# OPENMV4_wd.net
KiCad netlist of a schematic drawn in Altium Designer
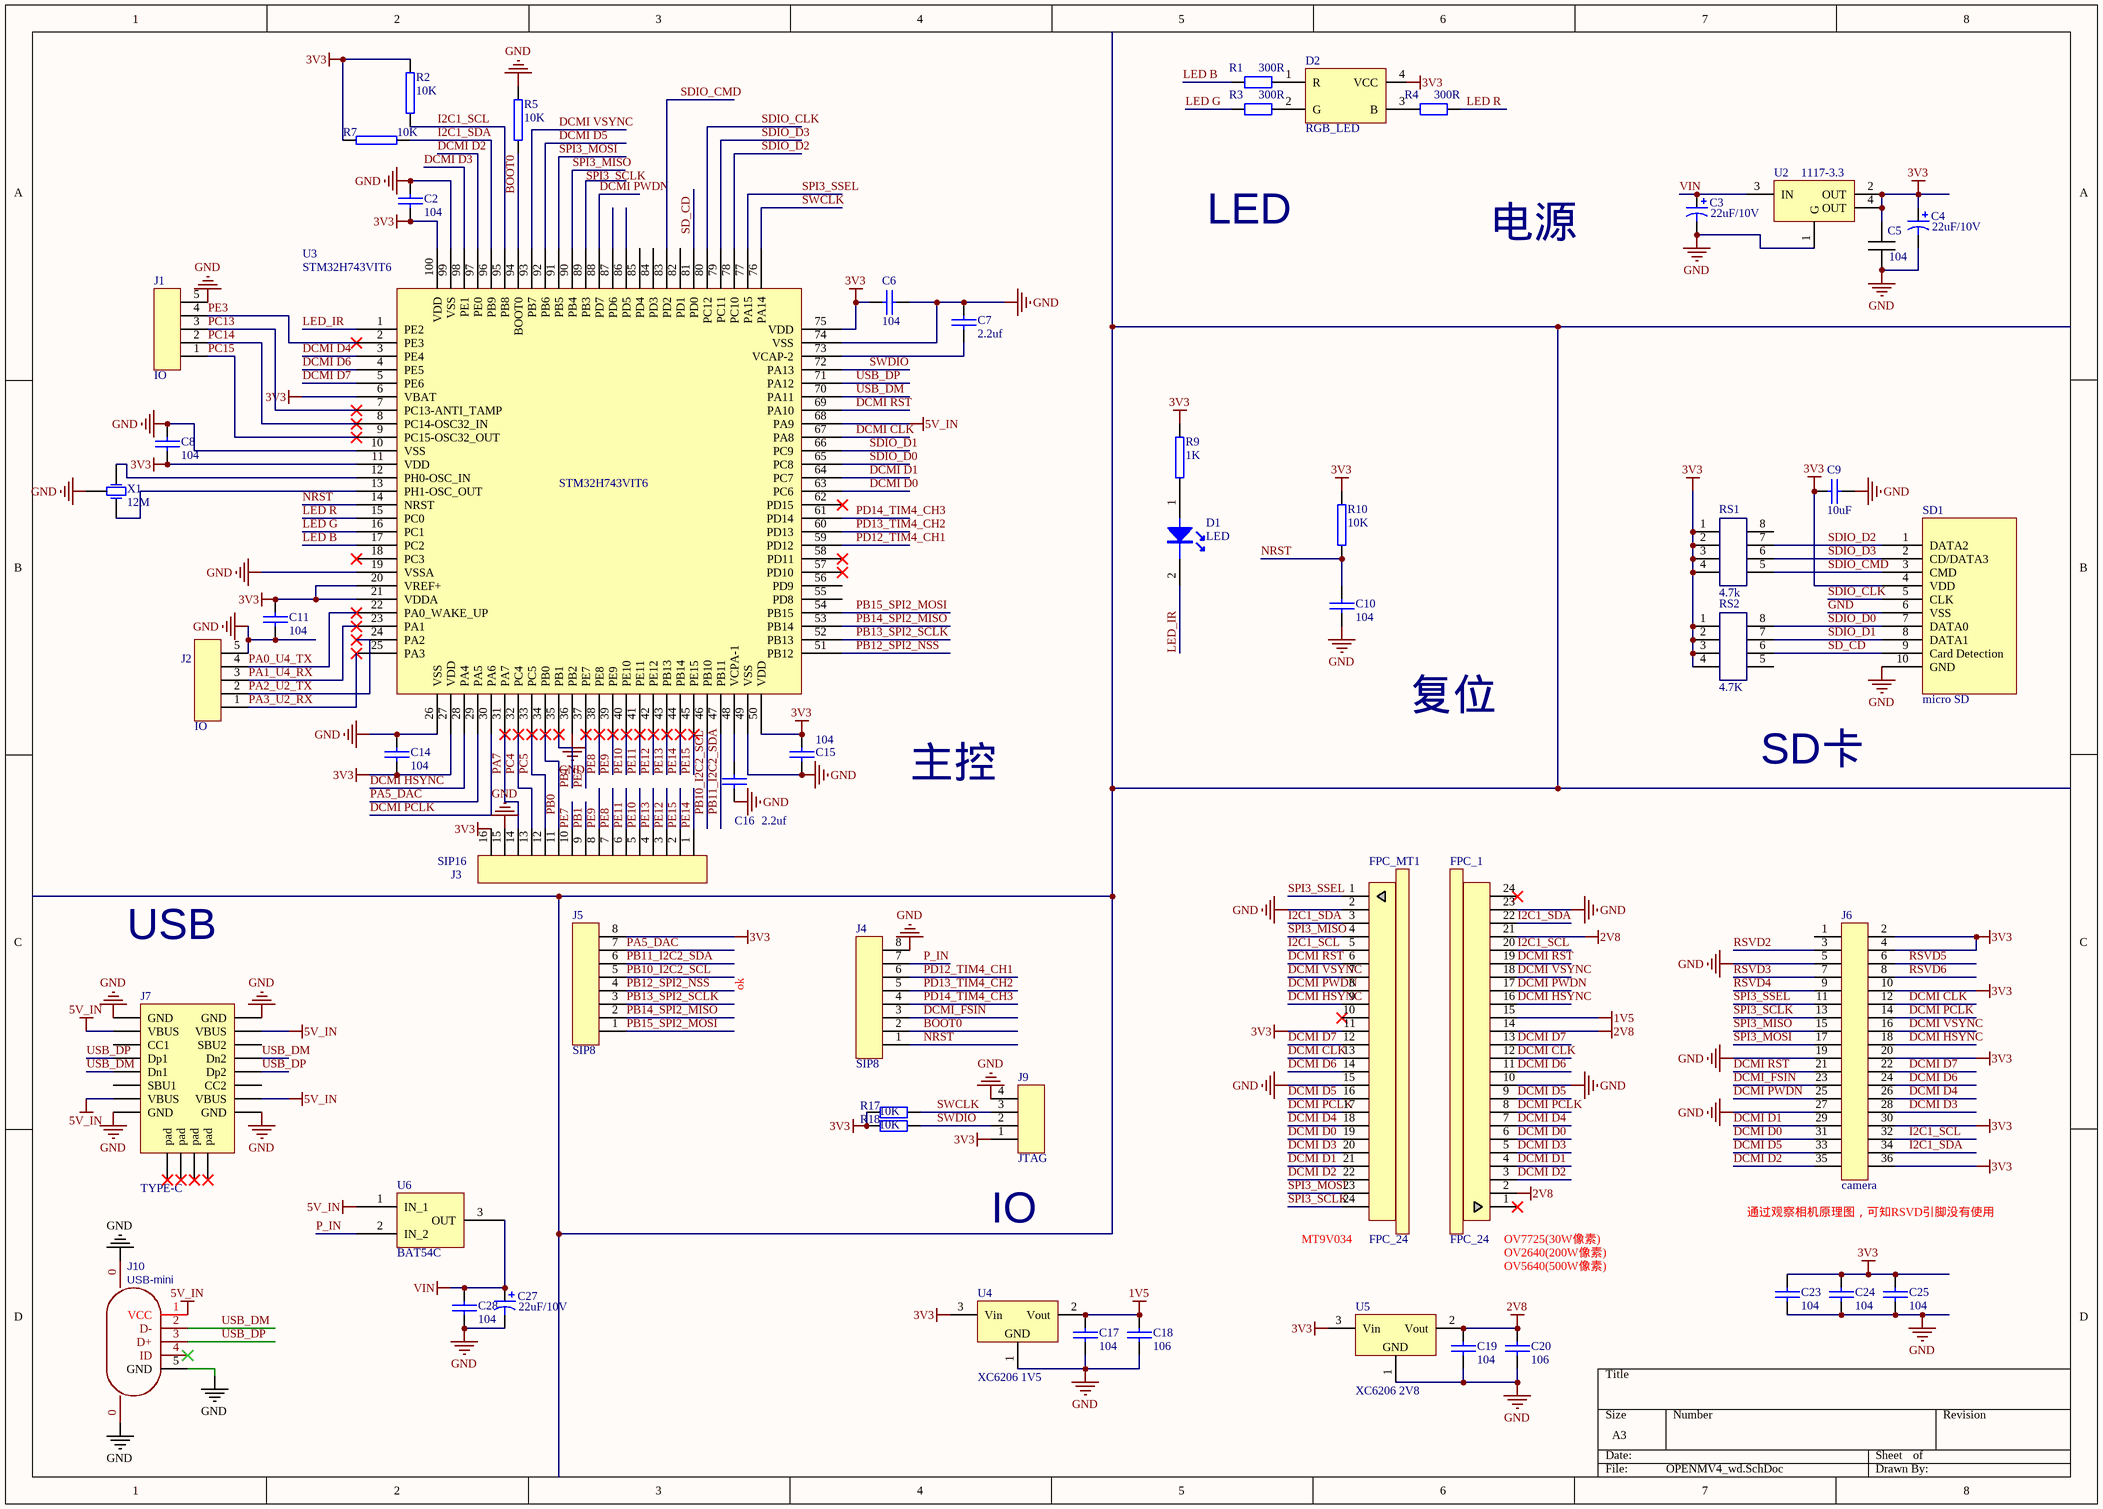
[diagram p0: OPENMV4_wd.SchDoc]

(export (version "E")
  (design (tool "Eeschema 10.0.6"))
  (components
    (comp (ref "C2") (value "104") (footprint "0805C") (libsource (lib "自创 (1)") (part "CAP")))
    (comp (ref "C3")
      (value "22uF/10V")
      (footprint "1210")
      (description "Polarized Capacitor (Radial)")
      (fields (field (name "Comment") "47uF") (field (name "PUBLISHER") "Altium Limited"))
      (libsource (lib "Miscellaneous Devices") (part "Cap Pol1"))
    )
    (comp (ref "C4")
      (value "22uF/10V")
      (footprint "1210")
      (description "Polarized Capacitor (Radial)")
      (fields (field (name "Comment") "47uF") (field (name "PUBLISHER") "Altium Limited"))
      (libsource (lib "Miscellaneous Devices") (part "Cap Pol1"))
    )
    (comp (ref "C5") (value "104") (footprint "0805C") (libsource (lib "NT-SchLibrary") (part "CAP104")))
    (comp (ref "C6") (value "104") (footprint "0805C") (libsource (lib "自创 (1)") (part "CAP")))
    (comp (ref "C7") (value "2.2uf") (footprint "0805C") (libsource (lib "自创 (1)") (part "CAP")))
    (comp (ref "C8") (value "104") (footprint "0805C") (libsource (lib "自创 (1)") (part "CAP")))
    (comp (ref "C9") (value "10uF") (footprint "LC-0805_C") (libsource (lib "自创 (1)") (part "CAP")))
    (comp (ref "C10") (value "104") (footprint "0805C") (libsource (lib "自创 (1)") (part "CAP")))
    (comp (ref "C11") (value "104") (footprint "0805C") (libsource (lib "自创 (1)") (part "CAP")))
    (comp (ref "C14") (value "104") (footprint "0805C") (libsource (lib "自创 (1)") (part "CAP")))
    (comp (ref "C15") (value "104") (footprint "0805C") (libsource (lib "自创 (1)") (part "CAP")))
    (comp (ref "C16") (value "2.2uf") (footprint "0805C") (libsource (lib "自创 (1)") (part "CAP")))
    (comp (ref "C17") (value "104") (footprint "0805C") (libsource (lib "XKZ") (part "CAP")))
    (comp (ref "C18") (value "106") (footprint "0805C") (libsource (lib "XKZ") (part "CAP")))
    (comp (ref "C19") (value "104") (footprint "0805C") (libsource (lib "XKZ") (part "CAP")))
    (comp (ref "C20") (value "106") (footprint "0805C") (libsource (lib "XKZ") (part "CAP")))
    (comp (ref "C23") (value "104") (footprint "0805C") (libsource (lib "自创 (1)") (part "CAP")))
    (comp (ref "C24") (value "104") (footprint "0805C") (libsource (lib "自创 (1)") (part "CAP")))
    (comp (ref "C25") (value "104") (footprint "0805C") (libsource (lib "自创 (1)") (part "CAP")))
    (comp (ref "C27")
      (value "22uF/10V")
      (footprint "1210")
      (description "Polarized Capacitor (Radial)")
      (fields (field (name "Comment") "47uF") (field (name "PUBLISHER") "Altium Limited"))
      (libsource (lib "Miscellaneous Devices") (part "Cap Pol1"))
    )
    (comp (ref "C28") (value "104") (footprint "0805C") (libsource (lib "自创 (1)") (part "CAP")))
    (comp (ref "D1") (value "LED") (footprint "0805D") (libsource (lib "WindSCH") (part "LED")))
    (comp (ref "D2")
      (value "RGB_LED")
      (footprint "LED_3528_RGB")
      (description "三色高亮LED")
      (libsource (lib "NT-SchLibrary") (part "RGB_LED"))
    )
    (comp (ref "FPC_1") (value "FPC_24") (footprint "FPC_24") (libsource (lib "") (part "FPC_24_1")))
    (comp (ref "FPC_MT1") (value "FPC_24") (footprint "FPC_24") (libsource (lib "XKZ") (part "FPC_24")))
    (comp (ref "J1") (value "IO") (footprint "SIP5") (libsource (lib "WindSCH") (part "SIP5")))
    (comp (ref "J2") (value "IO") (footprint "SIP5") (libsource (lib "WindSCH") (part "SIP5")))
    (comp (ref "J3") (value "SIP16") (footprint "IDC16") (libsource (lib "WindSCH") (part "SIP16")))
    (comp (ref "J4") (value "SIP8") (footprint "sip8") (libsource (lib "WindSCH") (part "SIP8")))
    (comp (ref "J5") (value "SIP8") (footprint "sip8") (libsource (lib "WindSCH") (part "SIP8")))
    (comp (ref "J6") (value "camera") (footprint "DF12-36-DS") (libsource (lib "WindSCH") (part "IDC36")))
    (comp (ref "J7") (value "TYPE-C") (footprint "USB Type-C-16Pin_A") (libsource (lib "XKZ") (part "USB_C")))
    (comp (ref "J9") (value "JTAG") (footprint "SIP4-1") (libsource (lib "WindSCH") (part "SIP4")))
    (comp (ref "J10")
      (value "USB-mini")
      (footprint "USB-MINI")
      (fields
        (field (name "BOM_MANUFACTURER PART") "USB-CON-MICRO-B-5S")
        (field (name "BOM_SUPPLIER PART") "C40954")
      )
      (libsource (lib "crazepony2_1") (part "USB-CON-MICRO-B-5S"))
    )
    (comp (ref "R1")
      (value "300R")
      (footprint "0805R")
      (description "Resistor")
      (fields (field (name "Comment") "1K") (field (name "PUBLISHER") "Altium Limited"))
      (libsource (lib "Miscellaneous Devices") (part "Res2"))
    )
    (comp (ref "R2") (value "10K") (footprint "0805R") (libsource (lib "自创 (1)") (part "RES")))
    (comp (ref "R3")
      (value "300R")
      (footprint "0805R")
      (description "Resistor")
      (fields (field (name "Comment") "1K") (field (name "PUBLISHER") "Altium Limited"))
      (libsource (lib "Miscellaneous Devices") (part "Res2"))
    )
    (comp (ref "R4")
      (value "300R")
      (footprint "0805R")
      (description "Resistor")
      (fields (field (name "Comment") "1K") (field (name "PUBLISHER") "Altium Limited"))
      (libsource (lib "Miscellaneous Devices") (part "Res2"))
    )
    (comp (ref "R5") (value "10K") (footprint "0805R") (libsource (lib "自创 (1)") (part "RES")))
    (comp (ref "R7") (value "10K") (footprint "0805R") (libsource (lib "自创 (1)") (part "RES")))
    (comp (ref "R9") (value "1K") (footprint "0805R") (libsource (lib "自创 (1)") (part "RES")))
    (comp (ref "R10") (value "10K") (footprint "0805R") (libsource (lib "自创 (1)") (part "RES")))
    (comp (ref "R17")
      (value "10K")
      (footprint "0805R")
      (description "Resistor")
      (fields (field (name "PUBLISHER") "Altium Limited"))
      (libsource (lib "") (part "Res2_1"))
    )
    (comp (ref "R18")
      (value "10K")
      (footprint "0805R")
      (description "Resistor")
      (fields (field (name "PUBLISHER") "Altium Limited"))
      (libsource (lib "") (part "Res2_1"))
    )
    (comp (ref "RS1") (value "4.7k") (footprint "0603*4") (libsource (lib "WindSCH") (part "RS")))
    (comp (ref "RS2") (value "4.7K") (footprint "0603*4") (libsource (lib "WindSCH") (part "RS")))
    (comp (ref "SD1") (value "micro SD") (footprint "TF卡座") (libsource (lib "XKZ") (part "micro SD")))
    (comp (ref "U2") (value "1117-3.3") (footprint "SOT223") (libsource (lib "WindSCH") (part "1117")))
    (comp (ref "U3")
      (value "STM32H743VIT6")
      (footprint "LQFP100 14x14_N")
      (libsource (lib "XKZ") (part "STM32H743VIT6"))
    )
    (comp (ref "U4")
      (value "XC6206 1V5")
      (footprint "SOT23-3N")
      (description "低压差线性稳压芯片")
      (fields (field (name "版权归属") "源创客"))
      (libsource (lib "XKZ") (part "XC6206P332MR"))
    )
    (comp (ref "U5")
      (value "XC6206 2V8")
      (footprint "SOT23-3N")
      (description "低压差线性稳压芯片")
      (fields (field (name "版权归属") "源创客"))
      (libsource (lib "XKZ") (part "XC6206P332MR"))
    )
    (comp (ref "U6") (value "BAT54C") (footprint "SOT23-3N") (libsource (lib "XKZ") (part "BAT54C")))
    (comp (ref "X1") (value "12M") (footprint "XTAL-3215-3P") (libsource (lib "XKZ") (part "XTAL_3P")))
  )
  (nets
    (net (code "1") (name "/BOOT0") (class "Default")
      (node (ref "J4") (pin "2") (pintype "passive"))
      (node (ref "R5") (pin "1") (pinfunction "1_1") (pintype "passive"))
      (node (ref "U3") (pin "94") (pinfunction "BOOT0_94") (pintype "passive"))
    )
    (net (code "2") (name "/DCMI CLK") (class "Default")
      (node (ref "FPC_1") (pin "12") (pinfunction "12_12") (pintype "passive"))
      (node (ref "FPC_MT1") (pin "13") (pinfunction "13_13") (pintype "passive"))
      (node (ref "J6") (pin "12") (pintype "passive"))
      (node (ref "U3") (pin "67") (pinfunction "PA8_67") (pintype "passive"))
    )
    (net (code "3") (name "/DCMI D0") (class "Default")
      (node (ref "FPC_1") (pin "6") (pinfunction "6_6") (pintype "passive"))
      (node (ref "FPC_MT1") (pin "19") (pinfunction "19_19") (pintype "passive"))
      (node (ref "J6") (pin "31") (pintype "passive"))
      (node (ref "U3") (pin "63") (pinfunction "PC6_63") (pintype "passive"))
    )
    (net (code "4") (name "/DCMI D1") (class "Default")
      (node (ref "FPC_1") (pin "4") (pinfunction "4_4") (pintype "passive"))
      (node (ref "FPC_MT1") (pin "21") (pinfunction "21_21") (pintype "passive"))
      (node (ref "J6") (pin "29") (pintype "passive"))
      (node (ref "U3") (pin "64") (pinfunction "PC7_64") (pintype "passive"))
    )
    (net (code "5") (name "/DCMI D2") (class "Default")
      (node (ref "FPC_1") (pin "3") (pinfunction "3_3") (pintype "passive"))
      (node (ref "FPC_MT1") (pin "22") (pinfunction "22_22") (pintype "passive"))
      (node (ref "J6") (pin "35") (pintype "passive"))
      (node (ref "U3") (pin "97") (pinfunction "PE0_97") (pintype "passive"))
    )
    (net (code "6") (name "/DCMI D3") (class "Default")
      (node (ref "FPC_1") (pin "5") (pinfunction "5_5") (pintype "passive"))
      (node (ref "FPC_MT1") (pin "20") (pinfunction "20_20") (pintype "passive"))
      (node (ref "J6") (pin "28") (pintype "passive"))
      (node (ref "U3") (pin "98") (pinfunction "PE1_98") (pintype "passive"))
    )
    (net (code "7") (name "/DCMI D4") (class "Default")
      (node (ref "FPC_1") (pin "7") (pinfunction "7_7") (pintype "passive"))
      (node (ref "FPC_MT1") (pin "18") (pinfunction "18_18") (pintype "passive"))
      (node (ref "J6") (pin "26") (pintype "passive"))
      (node (ref "U3") (pin "3") (pinfunction "PE4_3") (pintype "passive"))
    )
    (net (code "8") (name "/DCMI D5") (class "Default")
      (node (ref "FPC_1") (pin "9") (pinfunction "9_9") (pintype "passive"))
      (node (ref "FPC_MT1") (pin "16") (pinfunction "16_16") (pintype "passive"))
      (node (ref "J6") (pin "33") (pintype "passive"))
      (node (ref "U3") (pin "92") (pinfunction "PB6_92") (pintype "passive"))
    )
    (net (code "9") (name "/DCMI D6") (class "Default")
      (node (ref "FPC_1") (pin "11") (pinfunction "11_11") (pintype "passive"))
      (node (ref "FPC_MT1") (pin "14") (pinfunction "14_14") (pintype "passive"))
      (node (ref "J6") (pin "24") (pintype "passive"))
      (node (ref "U3") (pin "4") (pinfunction "PE5_4") (pintype "passive"))
    )
    (net (code "10") (name "/DCMI D7") (class "Default")
      (node (ref "FPC_1") (pin "13") (pinfunction "13_13") (pintype "passive"))
      (node (ref "FPC_MT1") (pin "12") (pinfunction "12_12") (pintype "passive"))
      (node (ref "J6") (pin "22") (pintype "passive"))
      (node (ref "U3") (pin "5") (pinfunction "PE6_5") (pintype "passive"))
    )
    (net (code "11") (name "/DCMI HSYNC") (class "Default")
      (node (ref "FPC_1") (pin "16") (pinfunction "16_16") (pintype "passive"))
      (node (ref "FPC_MT1") (pin "9") (pinfunction "9_9") (pintype "passive"))
      (node (ref "J6") (pin "18") (pintype "passive"))
      (node (ref "U3") (pin "28") (pinfunction "PA4_28") (pintype "passive"))
    )
    (net (code "12") (name "/DCMI PCLK") (class "Default")
      (node (ref "FPC_1") (pin "8") (pinfunction "8_8") (pintype "passive"))
      (node (ref "FPC_MT1") (pin "17") (pinfunction "17_17") (pintype "passive"))
      (node (ref "J6") (pin "14") (pintype "passive"))
      (node (ref "U3") (pin "30") (pinfunction "PA6_30") (pintype "passive"))
    )
    (net (code "13") (name "/DCMI PWDN") (class "Default")
      (node (ref "FPC_1") (pin "17") (pinfunction "17_17") (pintype "passive"))
      (node (ref "FPC_MT1") (pin "8") (pinfunction "8_8") (pintype "passive"))
      (node (ref "J6") (pin "25") (pintype "passive"))
      (node (ref "U3") (pin "88") (pinfunction "PD7_88") (pintype "passive"))
    )
    (net (code "14") (name "/DCMI RST") (class "Default")
      (node (ref "FPC_1") (pin "19") (pinfunction "19_19") (pintype "passive"))
      (node (ref "FPC_MT1") (pin "6") (pinfunction "6_6") (pintype "passive"))
      (node (ref "J6") (pin "21") (pintype "passive"))
      (node (ref "U3") (pin "69") (pinfunction "PA10_69") (pintype "passive"))
    )
    (net (code "15") (name "/DCMI VSYNC") (class "Default")
      (node (ref "FPC_1") (pin "18") (pinfunction "18_18") (pintype "passive"))
      (node (ref "FPC_MT1") (pin "7") (pinfunction "7_7") (pintype "passive"))
      (node (ref "J6") (pin "16") (pintype "passive"))
      (node (ref "U3") (pin "93") (pinfunction "PB7_93") (pintype "passive"))
    )
    (net (code "16") (name "/DCMI_FSIN") (class "Default")
      (node (ref "J4") (pin "3") (pintype "passive"))
      (node (ref "J6") (pin "23") (pintype "passive"))
    )
    (net (code "17") (name "/I2C1_SCL") (class "Default")
      (node (ref "FPC_1") (pin "20") (pinfunction "20_20") (pintype "passive"))
      (node (ref "FPC_MT1") (pin "5") (pinfunction "5_5") (pintype "passive"))
      (node (ref "J6") (pin "32") (pintype "passive"))
      (node (ref "R2") (pin "1") (pinfunction "1_1") (pintype "passive"))
      (node (ref "U3") (pin "95") (pinfunction "PB8_95") (pintype "passive"))
    )
    (net (code "18") (name "/I2C1_SDA") (class "Default")
      (node (ref "FPC_1") (pin "22") (pinfunction "22_22") (pintype "passive"))
      (node (ref "FPC_MT1") (pin "3") (pinfunction "3_3") (pintype "passive"))
      (node (ref "J6") (pin "34") (pintype "passive"))
      (node (ref "R7") (pin "2") (pinfunction "2_2") (pintype "passive"))
      (node (ref "U3") (pin "96") (pinfunction "PB9_96") (pintype "passive"))
    )
    (net (code "19") (name "/LED B") (class "Default")
      (node (ref "R1") (pin "1") (pinfunction "1_1") (pintype "passive"))
      (node (ref "U3") (pin "17") (pinfunction "PC2_17") (pintype "passive"))
    )
    (net (code "20") (name "/LED G") (class "Default")
      (node (ref "R3") (pin "1") (pinfunction "1_1") (pintype "passive"))
      (node (ref "U3") (pin "16") (pinfunction "PC1_16") (pintype "passive"))
    )
    (net (code "21") (name "/LED R") (class "Default")
      (node (ref "R4") (pin "2") (pinfunction "2_2") (pintype "passive"))
      (node (ref "U3") (pin "15") (pinfunction "PC0_15") (pintype "passive"))
    )
    (net (code "22") (name "/LED_IR") (class "Default")
      (node (ref "D1") (pin "2") (pinfunction "2_2") (pintype "passive"))
      (node (ref "U3") (pin "1") (pinfunction "PE2_1") (pintype "passive"))
    )
    (net (code "23") (name "/NRST") (class "Default")
      (node (ref "C10") (pin "2") (pinfunction "2_2") (pintype "passive"))
      (node (ref "J4") (pin "1") (pintype "passive"))
      (node (ref "R10") (pin "2") (pinfunction "2_2") (pintype "passive"))
      (node (ref "U3") (pin "14") (pinfunction "NRST_14") (pintype "passive"))
    )
    (net (code "24") (name "/PA0_U4_TX") (class "Default")
      (node (ref "J2") (pin "4") (pintype "passive"))
      (node (ref "U3") (pin "22") (pinfunction "PA0_WAKE_UP_22") (pintype "passive"))
    )
    (net (code "25") (name "/PA1_U4_RX") (class "Default")
      (node (ref "J2") (pin "3") (pintype "passive"))
      (node (ref "U3") (pin "23") (pinfunction "PA1_23") (pintype "passive"))
    )
    (net (code "26") (name "/PA2_U2_TX") (class "Default")
      (node (ref "J2") (pin "2") (pintype "passive"))
      (node (ref "U3") (pin "24") (pinfunction "PA2_24") (pintype "passive"))
    )
    (net (code "27") (name "/PA3_U2_RX") (class "Default")
      (node (ref "J2") (pin "1") (pintype "passive"))
      (node (ref "U3") (pin "25") (pinfunction "PA3_25") (pintype "passive"))
    )
    (net (code "28") (name "/PA5_DAC") (class "Default")
      (node (ref "J5") (pin "7") (pintype "passive"))
      (node (ref "U3") (pin "29") (pinfunction "PA5_29") (pintype "passive"))
    )
    (net (code "29") (name "/PA7") (class "Default")
      (node (ref "J3") (pin "14") (pintype "passive"))
      (node (ref "U3") (pin "31") (pinfunction "PA7_31") (pintype "passive"))
    )
    (net (code "30") (name "/PB0") (class "Default")
      (node (ref "J3") (pin "11") (pintype "passive"))
      (node (ref "U3") (pin "34") (pinfunction "PB0_34") (pintype "passive"))
    )
    (net (code "31") (name "/PB1") (class "Default")
      (node (ref "J3") (pin "9") (pintype "passive"))
      (node (ref "U3") (pin "35") (pinfunction "PB1_35") (pintype "passive"))
    )
    (net (code "32") (name "/PB10_I2C2_SCL") (class "Default")
      (node (ref "J5") (pin "5") (pintype "passive"))
      (node (ref "U3") (pin "46") (pinfunction "PB10_46") (pintype "passive"))
    )
    (net (code "33") (name "/PB11_I2C2_SDA") (class "Default")
      (node (ref "J5") (pin "6") (pintype "passive"))
      (node (ref "U3") (pin "47") (pinfunction "PB11_47") (pintype "passive"))
    )
    (net (code "34") (name "/PB12_SPI2_NSS") (class "Default")
      (node (ref "J5") (pin "4") (pintype "passive"))
      (node (ref "U3") (pin "51") (pinfunction "PB12_51") (pintype "passive"))
    )
    (net (code "35") (name "/PB13_SPI2_SCLK") (class "Default")
      (node (ref "J5") (pin "3") (pintype "passive"))
      (node (ref "U3") (pin "52") (pinfunction "PB13_52") (pintype "passive"))
    )
    (net (code "36") (name "/PB14_SPI2_MISO") (class "Default")
      (node (ref "J5") (pin "2") (pintype "passive"))
      (node (ref "U3") (pin "53") (pinfunction "PB14_53") (pintype "passive"))
    )
    (net (code "37") (name "/PB15_SPI2_MOSI") (class "Default")
      (node (ref "J5") (pin "1") (pintype "passive"))
      (node (ref "U3") (pin "54") (pinfunction "PB15_54") (pintype "passive"))
    )
    (net (code "38") (name "/PC4") (class "Default")
      (node (ref "J3") (pin "13") (pintype "passive"))
      (node (ref "U3") (pin "32") (pinfunction "PC4_32") (pintype "passive"))
    )
    (net (code "39") (name "/PC5") (class "Default")
      (node (ref "J3") (pin "12") (pintype "passive"))
      (node (ref "U3") (pin "33") (pinfunction "PC5_33") (pintype "passive"))
    )
    (net (code "40") (name "/PC13") (class "Default")
      (node (ref "J1") (pin "3") (pintype "passive"))
      (node (ref "U3") (pin "7") (pinfunction "PC13-ANTI_TAMP_7") (pintype "passive"))
    )
    (net (code "41") (name "/PC14") (class "Default")
      (node (ref "J1") (pin "2") (pintype "passive"))
      (node (ref "U3") (pin "8") (pinfunction "PC14-OSC32_IN_8") (pintype "passive"))
    )
    (net (code "42") (name "/PC15") (class "Default")
      (node (ref "J1") (pin "1") (pintype "passive"))
      (node (ref "U3") (pin "9") (pinfunction "PC15-OSC32_OUT_9") (pintype "passive"))
    )
    (net (code "43") (name "/PD12_TIM4_CH1") (class "Default")
      (node (ref "J4") (pin "6") (pintype "passive"))
      (node (ref "U3") (pin "59") (pinfunction "PD12_59") (pintype "passive"))
    )
    (net (code "44") (name "/PD13_TIM4_CH2") (class "Default")
      (node (ref "J4") (pin "5") (pintype "passive"))
      (node (ref "U3") (pin "60") (pinfunction "PD13_60") (pintype "passive"))
    )
    (net (code "45") (name "/PD14_TIM4_CH3") (class "Default")
      (node (ref "J4") (pin "4") (pintype "passive"))
      (node (ref "U3") (pin "61") (pinfunction "PD14_61") (pintype "passive"))
    )
    (net (code "46") (name "/PE3") (class "Default")
      (node (ref "J1") (pin "4") (pintype "passive"))
      (node (ref "U3") (pin "2") (pinfunction "PE3_2") (pintype "passive"))
    )
    (net (code "47") (name "/PE7") (class "Default")
      (node (ref "J3") (pin "10") (pintype "passive"))
      (node (ref "U3") (pin "37") (pinfunction "PE7_37") (pintype "passive"))
    )
    (net (code "48") (name "/PE8") (class "Default")
      (node (ref "J3") (pin "7") (pintype "passive"))
      (node (ref "U3") (pin "38") (pinfunction "PE8_38") (pintype "passive"))
    )
    (net (code "49") (name "/PE9") (class "Default")
      (node (ref "J3") (pin "8") (pintype "passive"))
      (node (ref "U3") (pin "39") (pinfunction "PE9_39") (pintype "passive"))
    )
    (net (code "50") (name "/PE10") (class "Default")
      (node (ref "J3") (pin "5") (pintype "passive"))
      (node (ref "U3") (pin "40") (pinfunction "PE10_40") (pintype "passive"))
    )
    (net (code "51") (name "/PE11") (class "Default")
      (node (ref "J3") (pin "6") (pintype "passive"))
      (node (ref "U3") (pin "41") (pinfunction "PE11_41") (pintype "passive"))
    )
    (net (code "52") (name "/PE12") (class "Default")
      (node (ref "J3") (pin "3") (pintype "passive"))
      (node (ref "U3") (pin "42") (pinfunction "PE12_42") (pintype "passive"))
    )
    (net (code "53") (name "/PE13") (class "Default")
      (node (ref "J3") (pin "4") (pintype "passive"))
      (node (ref "U3") (pin "43") (pinfunction "PB13_43") (pintype "passive"))
    )
    (net (code "54") (name "/PE14") (class "Default")
      (node (ref "J3") (pin "1") (pintype "passive"))
      (node (ref "U3") (pin "44") (pinfunction "PB14_44") (pintype "passive"))
    )
    (net (code "55") (name "/PE15") (class "Default")
      (node (ref "J3") (pin "2") (pintype "passive"))
      (node (ref "U3") (pin "45") (pinfunction "PE15_45") (pintype "passive"))
    )
    (net (code "56") (name "/P_IN") (class "Default")
      (node (ref "J4") (pin "7") (pintype "passive"))
      (node (ref "U6") (pin "2") (pinfunction "IN_2_2") (pintype "passive"))
    )
    (net (code "57") (name "/RSVD2") (class "Default") (node (ref "J6") (pin "3") (pintype "passive")))
    (net (code "58") (name "/RSVD3") (class "Default") (node (ref "J6") (pin "7") (pintype "passive")))
    (net (code "59") (name "/RSVD4") (class "Default") (node (ref "J6") (pin "9") (pintype "passive")))
    (net (code "60") (name "/RSVD5") (class "Default") (node (ref "J6") (pin "6") (pintype "passive")))
    (net (code "61") (name "/RSVD6") (class "Default") (node (ref "J6") (pin "8") (pintype "passive")))
    (net (code "62") (name "/SDIO_CLK") (class "Default")
      (node (ref "SD1") (pin "5") (pinfunction "CLK_5") (pintype "passive"))
      (node (ref "U3") (pin "80") (pinfunction "PC12_80") (pintype "passive"))
    )
    (net (code "63") (name "/SDIO_CMD") (class "Default")
      (node (ref "RS1") (pin "5") (pinfunction "21_5") (pintype "passive"))
      (node (ref "SD1") (pin "3") (pinfunction "CMD_3") (pintype "passive"))
      (node (ref "U3") (pin "83") (pinfunction "PD2_83") (pintype "passive"))
    )
    (net (code "64") (name "/SDIO_D0") (class "Default")
      (node (ref "RS2") (pin "8") (pinfunction "24_8") (pintype "passive"))
      (node (ref "SD1") (pin "7") (pinfunction "DATA0_7") (pintype "passive"))
      (node (ref "U3") (pin "65") (pinfunction "PC8_65") (pintype "passive"))
    )
    (net (code "65") (name "/SDIO_D1") (class "Default")
      (node (ref "RS2") (pin "7") (pinfunction "23_7") (pintype "passive"))
      (node (ref "SD1") (pin "8") (pinfunction "DATA1_8") (pintype "passive"))
      (node (ref "U3") (pin "66") (pinfunction "PC9_66") (pintype "passive"))
    )
    (net (code "66") (name "/SDIO_D2") (class "Default")
      (node (ref "RS1") (pin "7") (pinfunction "23_7") (pintype "passive"))
      (node (ref "SD1") (pin "1") (pinfunction "DATA2_1") (pintype "passive"))
      (node (ref "U3") (pin "78") (pinfunction "PC10_78") (pintype "passive"))
    )
    (net (code "67") (name "/SDIO_D3") (class "Default")
      (node (ref "RS1") (pin "6") (pinfunction "22_6") (pintype "passive"))
      (node (ref "SD1") (pin "2") (pinfunction "CD/DATA3_2") (pintype "passive"))
      (node (ref "U3") (pin "79") (pinfunction "PC11_79") (pintype "passive"))
    )
    (net (code "68") (name "/SD_CD") (class "Default")
      (node (ref "RS2") (pin "6") (pinfunction "22_6") (pintype "passive"))
      (node (ref "SD1") (pin "9") (pinfunction "Card_Detection_9") (pintype "passive"))
      (node (ref "U3") (pin "81") (pinfunction "PD0_81") (pintype "passive"))
    )
    (net (code "69") (name "/SPI3_MISO") (class "Default")
      (node (ref "FPC_MT1") (pin "4") (pinfunction "4_4") (pintype "passive"))
      (node (ref "J6") (pin "15") (pintype "passive"))
      (node (ref "U3") (pin "90") (pinfunction "PB4_90") (pintype "passive"))
    )
    (net (code "70") (name "/SPI3_MOSI") (class "Default")
      (node (ref "FPC_MT1") (pin "23") (pinfunction "23_23") (pintype "passive"))
      (node (ref "J6") (pin "17") (pintype "passive"))
      (node (ref "U3") (pin "91") (pinfunction "PB5_91") (pintype "passive"))
    )
    (net (code "71") (name "/SPI3_SCLK") (class "Default")
      (node (ref "FPC_MT1") (pin "24") (pinfunction "24_24") (pintype "passive"))
      (node (ref "J6") (pin "13") (pintype "passive"))
      (node (ref "U3") (pin "89") (pinfunction "PB3_89") (pintype "passive"))
    )
    (net (code "72") (name "/SPI3_SSEL") (class "Default")
      (node (ref "FPC_MT1") (pin "1") (pinfunction "1_1") (pintype "passive"))
      (node (ref "J6") (pin "11") (pintype "passive"))
      (node (ref "U3") (pin "77") (pinfunction "PA15_77") (pintype "passive"))
    )
    (net (code "73") (name "/SWCLK") (class "Default")
      (node (ref "J9") (pin "3") (pintype "passive"))
      (node (ref "R17") (pin "1") (pinfunction "1_1") (pintype "passive"))
      (node (ref "U3") (pin "76") (pinfunction "PA14_76") (pintype "passive"))
    )
    (net (code "74") (name "/SWDIO") (class "Default")
      (node (ref "J9") (pin "2") (pintype "passive"))
      (node (ref "R18") (pin "1") (pinfunction "1_1") (pintype "passive"))
      (node (ref "U3") (pin "72") (pinfunction "PA13_72") (pintype "passive"))
    )
    (net (code "75") (name "/USB_DM") (class "Default")
      (node (ref "J10") (pin "2") (pinfunction "D-_2") (pintype "passive"))
      (node (ref "J7") (pin "A7") (pinfunction "Dn1_A7") (pintype "passive"))
      (node (ref "J7") (pin "B7") (pinfunction "Dn2_B7") (pintype "passive"))
      (node (ref "U3") (pin "70") (pinfunction "PA11_70") (pintype "passive"))
    )
    (net (code "76") (name "/USB_DP") (class "Default")
      (node (ref "J10") (pin "3") (pinfunction "D+_3") (pintype "passive"))
      (node (ref "J7") (pin "A6") (pinfunction "Dp1_A6") (pintype "passive"))
      (node (ref "J7") (pin "B6") (pinfunction "Dp2_B6") (pintype "passive"))
      (node (ref "U3") (pin "71") (pinfunction "PA12_71") (pintype "passive"))
    )
    (net (code "77") (name "1V5") (class "Default")
      (node (ref "C17") (pin "1") (pinfunction "1_1") (pintype "passive"))
      (node (ref "C18") (pin "1") (pinfunction "1_1") (pintype "passive"))
      (node (ref "FPC_1") (pin "15") (pinfunction "15_15") (pintype "passive"))
      (node (ref "U4") (pin "2") (pinfunction "Vout_2") (pintype "passive"))
    )
    (net (code "78") (name "2V8") (class "Default")
      (node (ref "C19") (pin "1") (pinfunction "1_1") (pintype "passive"))
      (node (ref "C20") (pin "1") (pinfunction "1_1") (pintype "passive"))
      (node (ref "FPC_1") (pin "14") (pinfunction "14_14") (pintype "passive"))
      (node (ref "FPC_1") (pin "2") (pinfunction "2_2") (pintype "passive"))
      (node (ref "FPC_1") (pin "21") (pinfunction "21_21") (pintype "passive"))
      (node (ref "U5") (pin "2") (pinfunction "Vout_2") (pintype "passive"))
    )
    (net (code "79") (name "3V3") (class "Default")
      (node (ref "C11") (pin "1") (pinfunction "1_1") (pintype "passive"))
      (node (ref "C14") (pin "2") (pinfunction "2_2") (pintype "passive"))
      (node (ref "C15") (pin "2") (pinfunction "2_2") (pintype "passive"))
      (node (ref "C2") (pin "2") (pinfunction "2_2") (pintype "passive"))
      (node (ref "C23") (pin "1") (pinfunction "1_1") (pintype "passive"))
      (node (ref "C24") (pin "1") (pinfunction "1_1") (pintype "passive"))
      (node (ref "C25") (pin "1") (pinfunction "1_1") (pintype "passive"))
      (node (ref "C4") (pin "1") (pinfunction "1_1") (pintype "passive"))
      (node (ref "C5") (pin "2") (pinfunction "2_2") (pintype "passive"))
      (node (ref "C6") (pin "2") (pinfunction "2_2") (pintype "passive"))
      (node (ref "C8") (pin "2") (pinfunction "2_2") (pintype "passive"))
      (node (ref "C9") (pin "2") (pinfunction "2_2") (pintype "passive"))
      (node (ref "D2") (pin "4") (pinfunction "VCC_4") (pintype "passive"))
      (node (ref "FPC_MT1") (pin "11") (pinfunction "11_11") (pintype "passive"))
      (node (ref "J3") (pin "16") (pintype "passive"))
      (node (ref "J5") (pin "8") (pintype "passive"))
      (node (ref "J6") (pin "10") (pintype "passive"))
      (node (ref "J6") (pin "2") (pintype "passive"))
      (node (ref "J6") (pin "20") (pintype "passive"))
      (node (ref "J6") (pin "30") (pintype "passive"))
      (node (ref "J6") (pin "36") (pintype "passive"))
      (node (ref "J6") (pin "4") (pintype "passive"))
      (node (ref "J9") (pin "1") (pintype "passive"))
      (node (ref "R10") (pin "1") (pinfunction "1_1") (pintype "passive"))
      (node (ref "R17") (pin "2") (pinfunction "2_2") (pintype "passive"))
      (node (ref "R18") (pin "2") (pinfunction "2_2") (pintype "passive"))
      (node (ref "R2") (pin "2") (pinfunction "2_2") (pintype "passive"))
      (node (ref "R7") (pin "1") (pinfunction "1_1") (pintype "passive"))
      (node (ref "R9") (pin "1") (pinfunction "1_1") (pintype "passive"))
      (node (ref "RS1") (pin "1") (pinfunction "17_1") (pintype "passive"))
      (node (ref "RS1") (pin "2") (pinfunction "18_2") (pintype "passive"))
      (node (ref "RS1") (pin "3") (pinfunction "19_3") (pintype "passive"))
      (node (ref "RS1") (pin "4") (pinfunction "20_4") (pintype "passive"))
      (node (ref "RS2") (pin "1") (pinfunction "17_1") (pintype "passive"))
      (node (ref "RS2") (pin "2") (pinfunction "18_2") (pintype "passive"))
      (node (ref "RS2") (pin "3") (pinfunction "19_3") (pintype "passive"))
      (node (ref "RS2") (pin "4") (pinfunction "20_4") (pintype "passive"))
      (node (ref "SD1") (pin "4") (pinfunction "VDD_4") (pintype "passive"))
      (node (ref "U2") (pin "2") (pinfunction "OUT_2") (pintype "passive"))
      (node (ref "U2") (pin "4") (pinfunction "OUT_4") (pintype "passive"))
      (node (ref "U3") (pin "100") (pinfunction "VDD_100") (pintype "passive"))
      (node (ref "U3") (pin "11") (pinfunction "VDD_11") (pintype "passive"))
      (node (ref "U3") (pin "20") (pinfunction "VREF+_20") (pintype "passive"))
      (node (ref "U3") (pin "21") (pinfunction "VDDA_21") (pintype "passive"))
      (node (ref "U3") (pin "27") (pinfunction "VDD_27") (pintype "passive"))
      (node (ref "U3") (pin "50") (pinfunction "VDD_50") (pintype "passive"))
      (node (ref "U3") (pin "6") (pinfunction "VBAT_6") (pintype "passive"))
      (node (ref "U3") (pin "75") (pinfunction "VDD_75") (pintype "passive"))
      (node (ref "U4") (pin "3") (pinfunction "Vin_3") (pintype "passive"))
      (node (ref "U5") (pin "3") (pinfunction "Vin_3") (pintype "passive"))
    )
    (net (code "80") (name "5V_IN") (class "Default")
      (node (ref "J10") (pin "1") (pinfunction "VCC_1") (pintype "passive"))
      (node (ref "J7") (pin "A4") (pinfunction "VBUS_A4") (pintype "passive"))
      (node (ref "J7") (pin "A9") (pinfunction "VBUS_A9") (pintype "passive"))
      (node (ref "J7") (pin "B4") (pinfunction "VBUS_B4") (pintype "passive"))
      (node (ref "J7") (pin "B9") (pinfunction "VBUS_B9") (pintype "passive"))
      (node (ref "U3") (pin "68") (pinfunction "PA9_68") (pintype "passive"))
      (node (ref "U6") (pin "1") (pinfunction "IN_1_1") (pintype "passive"))
    )
    (net (code "81") (name "GND") (class "Default")
      (node (ref "C10") (pin "1") (pinfunction "1_1") (pintype "passive"))
      (node (ref "C11") (pin "2") (pinfunction "2_2") (pintype "passive"))
      (node (ref "C14") (pin "1") (pinfunction "1_1") (pintype "passive"))
      (node (ref "C15") (pin "1") (pinfunction "1_1") (pintype "passive"))
      (node (ref "C16") (pin "2") (pinfunction "2_2") (pintype "passive"))
      (node (ref "C17") (pin "2") (pinfunction "2_2") (pintype "passive"))
      (node (ref "C18") (pin "2") (pinfunction "2_2") (pintype "passive"))
      (node (ref "C19") (pin "2") (pinfunction "2_2") (pintype "passive"))
      (node (ref "C2") (pin "1") (pinfunction "1_1") (pintype "passive"))
      (node (ref "C20") (pin "2") (pinfunction "2_2") (pintype "passive"))
      (node (ref "C23") (pin "2") (pinfunction "2_2") (pintype "passive"))
      (node (ref "C24") (pin "2") (pinfunction "2_2") (pintype "passive"))
      (node (ref "C25") (pin "2") (pinfunction "2_2") (pintype "passive"))
      (node (ref "C27") (pin "2") (pinfunction "2_2") (pintype "passive"))
      (node (ref "C28") (pin "2") (pinfunction "2_2") (pintype "passive"))
      (node (ref "C3") (pin "2") (pinfunction "2_2") (pintype "passive"))
      (node (ref "C4") (pin "2") (pinfunction "2_2") (pintype "passive"))
      (node (ref "C5") (pin "1") (pinfunction "1_1") (pintype "passive"))
      (node (ref "C6") (pin "1") (pinfunction "1_1") (pintype "passive"))
      (node (ref "C7") (pin "2") (pinfunction "2_2") (pintype "passive"))
      (node (ref "C8") (pin "1") (pinfunction "1_1") (pintype "passive"))
      (node (ref "C9") (pin "1") (pinfunction "1_1") (pintype "passive"))
      (node (ref "FPC_1") (pin "10") (pinfunction "10_10") (pintype "passive"))
      (node (ref "FPC_1") (pin "23") (pinfunction "23_23") (pintype "passive"))
      (node (ref "FPC_MT1") (pin "15") (pinfunction "15_15") (pintype "passive"))
      (node (ref "FPC_MT1") (pin "2") (pinfunction "2_2") (pintype "passive"))
      (node (ref "J1") (pin "5") (pintype "passive"))
      (node (ref "J10") (pin "0") (pinfunction "SH4_0") (pintype "passive"))
      (node (ref "J10") (pin "5") (pinfunction "GND_5") (pintype "passive"))
      (node (ref "J2") (pin "5") (pintype "passive"))
      (node (ref "J3") (pin "15") (pintype "passive"))
      (node (ref "J4") (pin "8") (pintype "passive"))
      (node (ref "J6") (pin "19") (pintype "passive"))
      (node (ref "J6") (pin "27") (pintype "passive"))
      (node (ref "J6") (pin "5") (pintype "passive"))
      (node (ref "J7") (pin "A1") (pinfunction "GND_A1") (pintype "passive"))
      (node (ref "J7") (pin "A12") (pinfunction "GND_A12") (pintype "passive"))
      (node (ref "J7") (pin "B1") (pinfunction "GND_B1") (pintype "passive"))
      (node (ref "J7") (pin "B12") (pinfunction "GND_B12") (pintype "passive"))
      (node (ref "J9") (pin "4") (pintype "passive"))
      (node (ref "R5") (pin "2") (pinfunction "2_2") (pintype "passive"))
      (node (ref "SD1") (pin "10") (pinfunction "GND_10") (pintype "passive"))
      (node (ref "SD1") (pin "6") (pinfunction "VSS_6") (pintype "passive"))
      (node (ref "U2") (pin "1") (pinfunction "G_1") (pintype "passive"))
      (node (ref "U3") (pin "10") (pinfunction "VSS_10") (pintype "passive"))
      (node (ref "U3") (pin "19") (pinfunction "VSSA_19") (pintype "passive"))
      (node (ref "U3") (pin "26") (pinfunction "VSS_26") (pintype "passive"))
      (node (ref "U3") (pin "36") (pinfunction "PB2_36") (pintype "passive"))
      (node (ref "U3") (pin "49") (pinfunction "VSS_49") (pintype "passive"))
      (node (ref "U3") (pin "74") (pinfunction "VSS_74") (pintype "passive"))
      (node (ref "U3") (pin "99") (pinfunction "VSS_99") (pintype "passive"))
      (node (ref "U4") (pin "1") (pinfunction "GND_1") (pintype "passive"))
      (node (ref "U5") (pin "1") (pinfunction "GND_1") (pintype "passive"))
      (node (ref "X1") (pin "2") (pinfunction "2_2") (pintype "passive"))
    )
    (net (code "82") (name "Net-(D1-Pad1)") (class "Default")
      (node (ref "D1") (pin "1") (pinfunction "1_1") (pintype "passive"))
      (node (ref "R9") (pin "2") (pinfunction "2_2") (pintype "passive"))
    )
    (net (code "83") (name "Net-(D2-B)") (class "Default")
      (node (ref "D2") (pin "3") (pinfunction "B_3") (pintype "passive"))
      (node (ref "R4") (pin "1") (pinfunction "1_1") (pintype "passive"))
    )
    (net (code "84") (name "Net-(D2-G)") (class "Default")
      (node (ref "D2") (pin "2") (pinfunction "G_2") (pintype "passive"))
      (node (ref "R3") (pin "2") (pinfunction "2_2") (pintype "passive"))
    )
    (net (code "85") (name "Net-(D2-R)") (class "Default")
      (node (ref "D2") (pin "1") (pinfunction "R_1") (pintype "passive"))
      (node (ref "R1") (pin "2") (pinfunction "2_2") (pintype "passive"))
    )
    (net (code "86") (name "Net-(U3-PH0-OSC_IN)") (class "Default")
      (node (ref "U3") (pin "12") (pinfunction "PH0-OSC_IN_12") (pintype "passive"))
      (node (ref "X1") (pin "1") (pinfunction "1_1") (pintype "passive"))
    )
    (net (code "87") (name "Net-(U3-PH1-OSC_OUT)") (class "Default")
      (node (ref "U3") (pin "13") (pinfunction "PH1-OSC_OUT_13") (pintype "passive"))
      (node (ref "X1") (pin "3") (pinfunction "3_3") (pintype "passive"))
    )
    (net (code "88") (name "Net-(U3-VCAP-2)") (class "Default")
      (node (ref "C7") (pin "1") (pinfunction "1_1") (pintype "passive"))
      (node (ref "U3") (pin "73") (pinfunction "VCAP-2_73") (pintype "passive"))
    )
    (net (code "89") (name "Net-(U3-VCPA-1)") (class "Default")
      (node (ref "C16") (pin "1") (pinfunction "1_1") (pintype "passive"))
      (node (ref "U3") (pin "48") (pinfunction "VCPA-1_48") (pintype "passive"))
    )
    (net (code "90") (name "VIN") (class "Default")
      (node (ref "C27") (pin "1") (pinfunction "1_1") (pintype "passive"))
      (node (ref "C28") (pin "1") (pinfunction "1_1") (pintype "passive"))
      (node (ref "C3") (pin "1") (pinfunction "1_1") (pintype "passive"))
      (node (ref "U2") (pin "3") (pinfunction "IN_3") (pintype "passive"))
      (node (ref "U6") (pin "3") (pinfunction "OUT_3") (pintype "passive"))
    )
    (net (code "91") (name "unconnected-(FPC_1-Pad1)") (class "Default")
      (node (ref "FPC_1") (pin "1") (pinfunction "1_1") (pintype "passive+no_connect"))
    )
    (net (code "92") (name "unconnected-(FPC_1-Pad24)") (class "Default")
      (node (ref "FPC_1") (pin "24") (pinfunction "24_24") (pintype "passive+no_connect"))
    )
    (net (code "93") (name "unconnected-(FPC_MT1-Pad10)") (class "Default")
      (node (ref "FPC_MT1") (pin "10") (pinfunction "10_10") (pintype "passive+no_connect"))
    )
    (net (code "94") (name "unconnected-(J6-Pad1)") (class "Default")
      (node (ref "J6") (pin "1") (pintype "passive"))
    )
    (net (code "95") (name "unconnected-(J7-CC1-PadA5)") (class "Default")
      (node (ref "J7") (pin "A5") (pinfunction "CC1_A5") (pintype "passive"))
    )
    (net (code "96") (name "unconnected-(J7-CC2-PadB5)") (class "Default")
      (node (ref "J7") (pin "B5") (pinfunction "CC2_B5") (pintype "passive"))
    )
    (net (code "97") (name "unconnected-(J7-SBU1-PadA8)") (class "Default")
      (node (ref "J7") (pin "A8") (pinfunction "SBU1_A8") (pintype "passive"))
    )
    (net (code "98") (name "unconnected-(J7-SBU2-PadB8)") (class "Default")
      (node (ref "J7") (pin "B8") (pinfunction "SBU2_B8") (pintype "passive"))
    )
    (net (code "99") (name "unconnected-(J7-pad-Pad0)") (class "Default")
      (node (ref "J7") (pin "0") (pinfunction "pad_0") (pintype "passive+no_connect"))
    )
    (net (code "100") (name "unconnected-(J7-pad-Pad0)_1") (class "Default")
      (node (ref "J7") (pin "0") (pinfunction "pad_0") (pintype "passive+no_connect"))
    )
    (net (code "101") (name "unconnected-(J7-pad-Pad0)_2") (class "Default")
      (node (ref "J7") (pin "0") (pinfunction "pad_0") (pintype "passive+no_connect"))
    )
    (net (code "102") (name "unconnected-(J7-pad-Pad0)_3") (class "Default")
      (node (ref "J7") (pin "0") (pinfunction "pad_0") (pintype "passive+no_connect"))
    )
    (net (code "103") (name "unconnected-(J10-ID-Pad4)") (class "Default")
      (node (ref "J10") (pin "4") (pinfunction "ID_4") (pintype "passive+no_connect"))
    )
    (net (code "104") (name "unconnected-(RS1-24-Pad8)") (class "Default")
      (node (ref "RS1") (pin "8") (pinfunction "24_8") (pintype "passive"))
    )
    (net (code "105") (name "unconnected-(RS2-21-Pad5)") (class "Default")
      (node (ref "RS2") (pin "5") (pinfunction "21_5") (pintype "passive"))
    )
    (net (code "106") (name "unconnected-(U3-PC3-Pad18)") (class "Default")
      (node (ref "U3") (pin "18") (pinfunction "PC3_18") (pintype "passive+no_connect"))
    )
    (net (code "107") (name "unconnected-(U3-PD1-Pad82)") (class "Default")
      (node (ref "U3") (pin "82") (pinfunction "PD1_82") (pintype "passive"))
    )
    (net (code "108") (name "unconnected-(U3-PD3-Pad84)") (class "Default")
      (node (ref "U3") (pin "84") (pinfunction "PD3_84") (pintype "passive"))
    )
    (net (code "109") (name "unconnected-(U3-PD4-Pad85)") (class "Default")
      (node (ref "U3") (pin "85") (pinfunction "PD4_85") (pintype "passive"))
    )
    (net (code "110") (name "unconnected-(U3-PD5-Pad86)") (class "Default")
      (node (ref "U3") (pin "86") (pinfunction "PD5_86") (pintype "passive"))
    )
    (net (code "111") (name "unconnected-(U3-PD6-Pad87)") (class "Default")
      (node (ref "U3") (pin "87") (pinfunction "PD6_87") (pintype "passive"))
    )
    (net (code "112") (name "unconnected-(U3-PD8-Pad55)") (class "Default")
      (node (ref "U3") (pin "55") (pinfunction "PD8_55") (pintype "passive"))
    )
    (net (code "113") (name "unconnected-(U3-PD9-Pad56)") (class "Default")
      (node (ref "U3") (pin "56") (pinfunction "PD9_56") (pintype "passive"))
    )
    (net (code "114") (name "unconnected-(U3-PD10-Pad57)") (class "Default")
      (node (ref "U3") (pin "57") (pinfunction "PD10_57") (pintype "passive+no_connect"))
    )
    (net (code "115") (name "unconnected-(U3-PD11-Pad58)") (class "Default")
      (node (ref "U3") (pin "58") (pinfunction "PD11_58") (pintype "passive+no_connect"))
    )
    (net (code "116") (name "unconnected-(U3-PD15-Pad62)") (class "Default")
      (node (ref "U3") (pin "62") (pinfunction "PD15_62") (pintype "passive+no_connect"))
    )
  )
)
